# T04_Main_Board.net
KiCad netlist of a schematic drawn in EAGLE
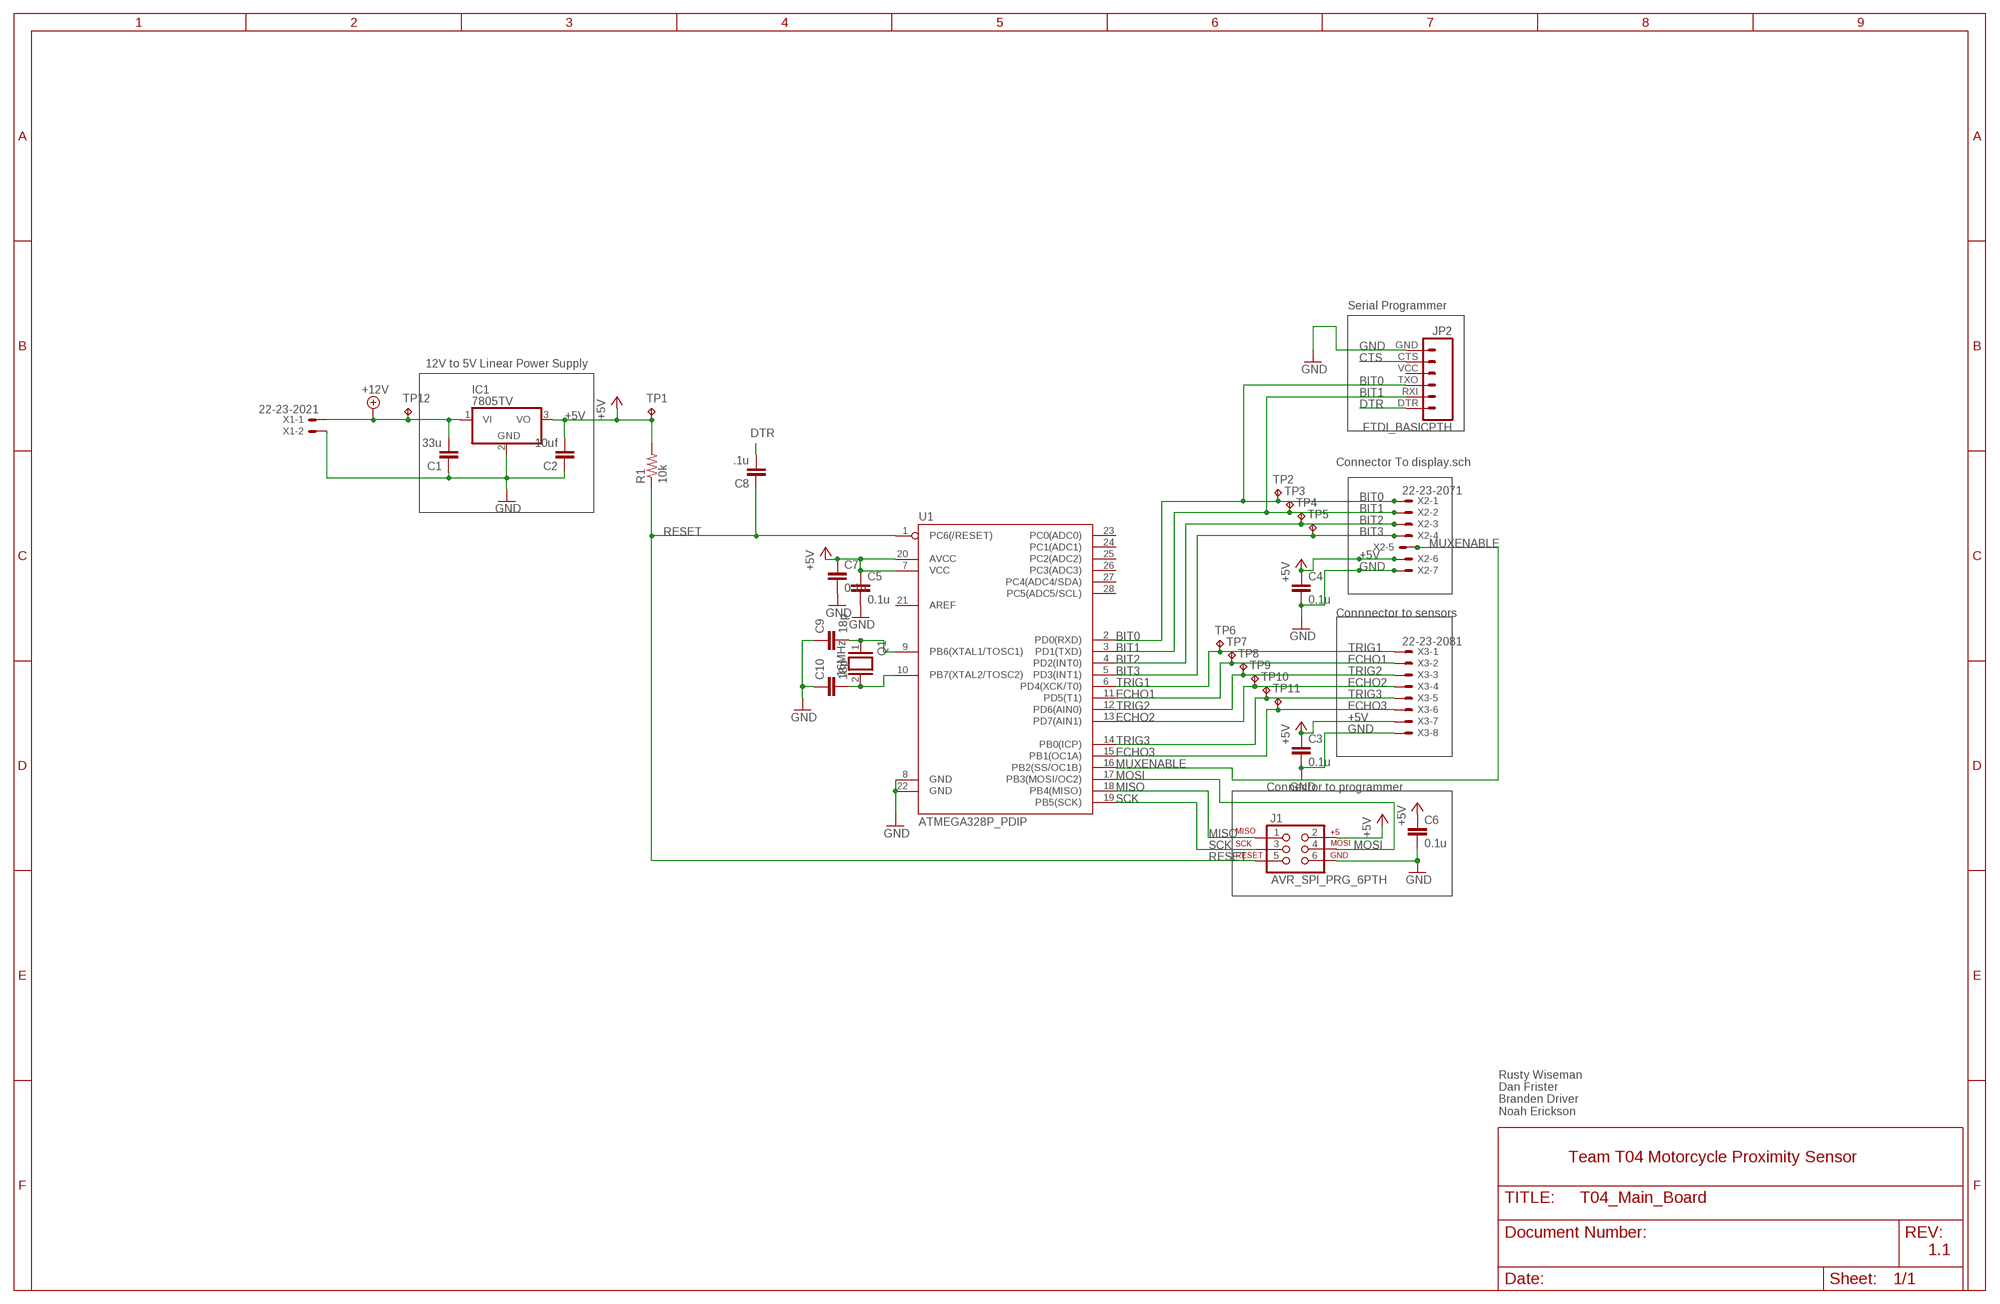
[diagram p0: schematic, sheet 1]

(export (version "E")
  (design (tool "Eeschema 10.0.6"))
  (components
    (comp (ref "C1")
      (value "33u")
      (footprint "eagle-import:C1206")
      (libsource (lib "eagle-import") (part "C-EUC1206"))
    )
    (comp (ref "C2")
      (value "10uf")
      (footprint "eagle-import:C1206")
      (libsource (lib "eagle-import") (part "C-EUC1206"))
    )
    (comp (ref "C3")
      (value "0.1u")
      (footprint "eagle-import:C1206")
      (libsource (lib "eagle-import") (part "C-EUC1206"))
    )
    (comp (ref "C4")
      (value "0.1u")
      (footprint "eagle-import:C1206")
      (libsource (lib "eagle-import") (part "C-EUC1206"))
    )
    (comp (ref "C5")
      (value "0.1u")
      (footprint "eagle-import:C1206")
      (libsource (lib "eagle-import") (part "C-EUC1206"))
    )
    (comp (ref "C6")
      (value "0.1u")
      (footprint "eagle-import:C1206")
      (libsource (lib "eagle-import") (part "C-EUC1206"))
    )
    (comp (ref "C7")
      (value "0.1u")
      (footprint "eagle-import:C1206")
      (libsource (lib "eagle-import") (part "C-EUC1206"))
    )
    (comp (ref "C8")
      (value ".1u")
      (footprint "eagle-import:C1206")
      (libsource (lib "eagle-import") (part "C-EUC1206"))
    )
    (comp (ref "C9")
      (value "18p")
      (footprint "eagle-import:C1206")
      (libsource (lib "eagle-import") (part "C-EUC1206"))
    )
    (comp (ref "C10")
      (value "18p")
      (footprint "eagle-import:C1206")
      (libsource (lib "eagle-import") (part "C-EUC1206"))
    )
    (comp (ref "IC1")
      (value "7805TV")
      (footprint "eagle-import:TO220V")
      (libsource (lib "eagle-import") (part "78TV05"))
    )
    (comp (ref "J1")
      (value "AVR_SPI_PRG_6PTH")
      (footprint "eagle-import:2X3")
      (libsource (lib "eagle-import") (part "AVR_SPI_PRG_6PTH"))
    )
    (comp (ref "JP2")
      (value "FTDI_BASICPTH")
      (footprint "eagle-import:FTDI_BASIC")
      (libsource (lib "eagle-import") (part "FTDI_BASICPTH"))
    )
    (comp (ref "Q1")
      (value "16MHz")
      (footprint "eagle-import:QS")
      (libsource (lib "eagle-import") (part "XTAL/S"))
    )
    (comp (ref "R1")
      (value "10k")
      (footprint "eagle-import:R1206")
      (libsource (lib "eagle-import") (part "R-US_R1206"))
    )
    (comp (ref "TP1")
      (value "TPB1,27")
      (footprint "eagle-import:B1,27")
      (libsource (lib "eagle-import") (part "TPB1,27"))
    )
    (comp (ref "TP2")
      (value "TPB1,27")
      (footprint "eagle-import:B1,27")
      (libsource (lib "eagle-import") (part "TPB1,27"))
    )
    (comp (ref "TP3")
      (value "TPB1,27")
      (footprint "eagle-import:B1,27")
      (libsource (lib "eagle-import") (part "TPB1,27"))
    )
    (comp (ref "TP4")
      (value "TPB1,27")
      (footprint "eagle-import:B1,27")
      (libsource (lib "eagle-import") (part "TPB1,27"))
    )
    (comp (ref "TP5")
      (value "TPB1,27")
      (footprint "eagle-import:B1,27")
      (libsource (lib "eagle-import") (part "TPB1,27"))
    )
    (comp (ref "TP6")
      (value "TPB1,27")
      (footprint "eagle-import:B1,27")
      (libsource (lib "eagle-import") (part "TPB1,27"))
    )
    (comp (ref "TP7")
      (value "TPB1,27")
      (footprint "eagle-import:B1,27")
      (libsource (lib "eagle-import") (part "TPB1,27"))
    )
    (comp (ref "TP8")
      (value "TPB1,27")
      (footprint "eagle-import:B1,27")
      (libsource (lib "eagle-import") (part "TPB1,27"))
    )
    (comp (ref "TP9")
      (value "TPB1,27")
      (footprint "eagle-import:B1,27")
      (libsource (lib "eagle-import") (part "TPB1,27"))
    )
    (comp (ref "TP10")
      (value "TPB1,27")
      (footprint "eagle-import:B1,27")
      (libsource (lib "eagle-import") (part "TPB1,27"))
    )
    (comp (ref "TP11")
      (value "TPB1,27")
      (footprint "eagle-import:B1,27")
      (libsource (lib "eagle-import") (part "TPB1,27"))
    )
    (comp (ref "TP12")
      (value "TPB1,27")
      (footprint "eagle-import:B1,27")
      (libsource (lib "eagle-import") (part "TPB1,27"))
    )
    (comp (ref "U1")
      (value "ATMEGA328P_PDIP")
      (footprint "eagle-import:DIL28-3")
      (libsource (lib "eagle-import") (part "ATMEGA328P_PDIP"))
    )
    (comp (ref "X1")
      (value "22-23-2021")
      (footprint "eagle-import:22-23-2021")
      (fields (field (name "MF") "MOLEX"))
      (libsource (lib "eagle-import") (part "22-23-2021"))
    )
    (comp (ref "X2")
      (value "22-23-2071")
      (footprint "eagle-import:22-23-2071")
      (fields (field (name "MF") "MOLEX"))
      (libsource (lib "eagle-import") (part "22-23-2071"))
    )
    (comp (ref "X3")
      (value "22-23-2081")
      (footprint "eagle-import:22-23-2081")
      (fields (field (name "MF") "MOLEX"))
      (libsource (lib "eagle-import") (part "22-23-2081"))
    )
  )
  (nets
    (net (code "1") (name "+5V") (class "Default")
      (node (ref "C2") (pin "2") (pinfunction "2_2") (pintype "passive"))
      (node (ref "C3") (pin "1") (pinfunction "1_1") (pintype "passive"))
      (node (ref "C4") (pin "1") (pinfunction "1_1") (pintype "passive"))
      (node (ref "C5") (pin "1") (pinfunction "1_1") (pintype "passive"))
      (node (ref "C6") (pin "1") (pinfunction "1_1") (pintype "passive"))
      (node (ref "C7") (pin "1") (pinfunction "1_1") (pintype "passive"))
      (node (ref "IC1") (pin "3") (pinfunction "VO_3") (pintype "passive"))
      (node (ref "J1") (pin "2") (pinfunction "2_2") (pintype "passive"))
      (node (ref "R1") (pin "2") (pinfunction "2_2") (pintype "passive"))
      (node (ref "TP1") (pin "TP") (pinfunction "TP_TP") (pintype "input"))
      (node (ref "U1") (pin "20") (pinfunction "AVCC_20") (pintype "bidirectional"))
      (node (ref "U1") (pin "7") (pinfunction "VCC_7") (pintype "bidirectional"))
      (node (ref "X2") (pin "6") (pinfunction "S_6") (pintype "passive"))
      (node (ref "X3") (pin "7") (pinfunction "S_7") (pintype "passive"))
    )
    (net (code "2") (name "+12V") (class "Default")
      (node (ref "C1") (pin "2") (pinfunction "2_2") (pintype "passive"))
      (node (ref "IC1") (pin "1") (pinfunction "VI_1") (pintype "input"))
      (node (ref "TP12") (pin "TP") (pinfunction "TP_TP") (pintype "input"))
      (node (ref "X1") (pin "1") (pinfunction "S_1") (pintype "passive"))
    )
    (net (code "3") (name "/BIT0") (class "Default")
      (node (ref "JP2") (pin "TXO") (pinfunction "3_TXO") (pintype "passive"))
      (node (ref "TP2") (pin "TP") (pinfunction "TP_TP") (pintype "input"))
      (node (ref "U1") (pin "2") (pinfunction "PD0(RXD)_2") (pintype "bidirectional"))
      (node (ref "X2") (pin "1") (pinfunction "S_1") (pintype "passive"))
    )
    (net (code "4") (name "/BIT1") (class "Default")
      (node (ref "JP2") (pin "RXI") (pinfunction "2_RXI") (pintype "passive"))
      (node (ref "TP3") (pin "TP") (pinfunction "TP_TP") (pintype "input"))
      (node (ref "U1") (pin "3") (pinfunction "PD1(TXD)_3") (pintype "bidirectional"))
      (node (ref "X2") (pin "2") (pinfunction "S_2") (pintype "passive"))
    )
    (net (code "5") (name "/BIT2") (class "Default")
      (node (ref "TP4") (pin "TP") (pinfunction "TP_TP") (pintype "input"))
      (node (ref "U1") (pin "4") (pinfunction "PD2(INT0)_4") (pintype "bidirectional"))
      (node (ref "X2") (pin "3") (pinfunction "S_3") (pintype "passive"))
    )
    (net (code "6") (name "/BIT3") (class "Default")
      (node (ref "TP5") (pin "TP") (pinfunction "TP_TP") (pintype "input"))
      (node (ref "U1") (pin "5") (pinfunction "PD3(INT1)_5") (pintype "bidirectional"))
      (node (ref "X2") (pin "4") (pinfunction "S_4") (pintype "passive"))
    )
    (net (code "7") (name "/CTS") (class "Default")
      (node (ref "JP2") (pin "CTS") (pinfunction "5_CTS") (pintype "passive"))
    )
    (net (code "8") (name "/DTR") (class "Default")
      (node (ref "C8") (pin "2") (pinfunction "2_2") (pintype "passive"))
      (node (ref "JP2") (pin "DTR") (pinfunction "1_DTR") (pintype "passive"))
    )
    (net (code "9") (name "/ECHO1") (class "Default")
      (node (ref "TP7") (pin "TP") (pinfunction "TP_TP") (pintype "input"))
      (node (ref "U1") (pin "11") (pinfunction "PD5(T1)_11") (pintype "bidirectional"))
      (node (ref "X3") (pin "2") (pinfunction "S_2") (pintype "passive"))
    )
    (net (code "10") (name "/ECHO2") (class "Default")
      (node (ref "TP9") (pin "TP") (pinfunction "TP_TP") (pintype "input"))
      (node (ref "U1") (pin "13") (pinfunction "PD7(AIN1)_13") (pintype "bidirectional"))
      (node (ref "X3") (pin "4") (pinfunction "S_4") (pintype "passive"))
    )
    (net (code "11") (name "/ECHO3") (class "Default")
      (node (ref "TP11") (pin "TP") (pinfunction "TP_TP") (pintype "input"))
      (node (ref "U1") (pin "15") (pinfunction "PB1(OC1A)_15") (pintype "bidirectional"))
      (node (ref "X3") (pin "6") (pinfunction "S_6") (pintype "passive"))
    )
    (net (code "12") (name "/MISO") (class "Default")
      (node (ref "J1") (pin "1") (pinfunction "1_1") (pintype "passive"))
      (node (ref "U1") (pin "18") (pinfunction "PB4(MISO)_18") (pintype "bidirectional"))
    )
    (net (code "13") (name "/MOSI") (class "Default")
      (node (ref "J1") (pin "4") (pinfunction "4_4") (pintype "passive"))
      (node (ref "U1") (pin "17") (pinfunction "PB3(MOSI/OC2)_17") (pintype "bidirectional"))
    )
    (net (code "14") (name "/MUXENABLE") (class "Default")
      (node (ref "U1") (pin "16") (pinfunction "PB2(SS/OC1B)_16") (pintype "bidirectional"))
      (node (ref "X2") (pin "5") (pinfunction "S_5") (pintype "passive"))
    )
    (net (code "15") (name "/RESET") (class "Default")
      (node (ref "C8") (pin "1") (pinfunction "1_1") (pintype "passive"))
      (node (ref "J1") (pin "5") (pinfunction "5_5") (pintype "passive"))
      (node (ref "R1") (pin "1") (pinfunction "1_1") (pintype "passive"))
      (node (ref "U1") (pin "1") (pinfunction "PC6(/RESET)_1") (pintype "bidirectional"))
    )
    (net (code "16") (name "/SCK") (class "Default")
      (node (ref "J1") (pin "3") (pinfunction "3_3") (pintype "passive"))
      (node (ref "U1") (pin "19") (pinfunction "PB5(SCK)_19") (pintype "bidirectional"))
    )
    (net (code "17") (name "/TRIG1") (class "Default")
      (node (ref "TP6") (pin "TP") (pinfunction "TP_TP") (pintype "input"))
      (node (ref "U1") (pin "6") (pinfunction "PD4(XCK/T0)_6") (pintype "bidirectional"))
      (node (ref "X3") (pin "1") (pinfunction "S_1") (pintype "passive"))
    )
    (net (code "18") (name "/TRIG2") (class "Default")
      (node (ref "TP8") (pin "TP") (pinfunction "TP_TP") (pintype "input"))
      (node (ref "U1") (pin "12") (pinfunction "PD6(AIN0)_12") (pintype "bidirectional"))
      (node (ref "X3") (pin "3") (pinfunction "S_3") (pintype "passive"))
    )
    (net (code "19") (name "/TRIG3") (class "Default")
      (node (ref "TP10") (pin "TP") (pinfunction "TP_TP") (pintype "input"))
      (node (ref "U1") (pin "14") (pinfunction "PB0(ICP)_14") (pintype "bidirectional"))
      (node (ref "X3") (pin "5") (pinfunction "S_5") (pintype "passive"))
    )
    (net (code "20") (name "GND") (class "Default")
      (node (ref "C1") (pin "1") (pinfunction "1_1") (pintype "passive"))
      (node (ref "C10") (pin "1") (pinfunction "1_1") (pintype "passive"))
      (node (ref "C2") (pin "1") (pinfunction "1_1") (pintype "passive"))
      (node (ref "C3") (pin "2") (pinfunction "2_2") (pintype "passive"))
      (node (ref "C4") (pin "2") (pinfunction "2_2") (pintype "passive"))
      (node (ref "C5") (pin "2") (pinfunction "2_2") (pintype "passive"))
      (node (ref "C6") (pin "2") (pinfunction "2_2") (pintype "passive"))
      (node (ref "C7") (pin "2") (pinfunction "2_2") (pintype "passive"))
      (node (ref "C9") (pin "1") (pinfunction "1_1") (pintype "passive"))
      (node (ref "IC1") (pin "2") (pinfunction "GND_2") (pintype "passive"))
      (node (ref "J1") (pin "6") (pinfunction "6_6") (pintype "passive"))
      (node (ref "JP2") (pin "GND") (pinfunction "6_GND") (pintype "passive"))
      (node (ref "U1") (pin "22") (pinfunction "GND_22") (pintype "bidirectional"))
      (node (ref "U1") (pin "8") (pinfunction "GND_8") (pintype "bidirectional"))
      (node (ref "X1") (pin "2") (pinfunction "S_2") (pintype "passive"))
      (node (ref "X2") (pin "7") (pinfunction "S_7") (pintype "passive"))
      (node (ref "X3") (pin "8") (pinfunction "S_8") (pintype "passive"))
    )
    (net (code "21") (name "Net-(U1-PB6(XTAL1{slash}TOSC1))") (class "Default")
      (node (ref "C9") (pin "2") (pinfunction "2_2") (pintype "passive"))
      (node (ref "Q1") (pin "1") (pinfunction "1_1") (pintype "passive"))
      (node (ref "U1") (pin "9") (pinfunction "PB6(XTAL1/TOSC1)_9") (pintype "bidirectional"))
    )
    (net (code "22") (name "Net-(U1-PB7(XTAL2{slash}TOSC2))") (class "Default")
      (node (ref "C10") (pin "2") (pinfunction "2_2") (pintype "passive"))
      (node (ref "Q1") (pin "2") (pinfunction "2_2") (pintype "passive"))
      (node (ref "U1") (pin "10") (pinfunction "PB7(XTAL2/TOSC2)_10") (pintype "bidirectional"))
    )
    (net (code "23") (name "unconnected-(JP2-4-PadVCC)") (class "Default")
      (node (ref "JP2") (pin "VCC") (pinfunction "4_VCC") (pintype "passive"))
    )
    (net (code "24") (name "unconnected-(U1-AREF-Pad21)") (class "Default")
      (node (ref "U1") (pin "21") (pinfunction "AREF_21") (pintype "bidirectional"))
    )
    (net (code "25") (name "unconnected-(U1-PC0(ADC0)-Pad23)") (class "Default")
      (node (ref "U1") (pin "23") (pinfunction "PC0(ADC0)_23") (pintype "bidirectional"))
    )
    (net (code "26") (name "unconnected-(U1-PC1(ADC1)-Pad24)") (class "Default")
      (node (ref "U1") (pin "24") (pinfunction "PC1(ADC1)_24") (pintype "bidirectional"))
    )
    (net (code "27") (name "unconnected-(U1-PC2(ADC2)-Pad25)") (class "Default")
      (node (ref "U1") (pin "25") (pinfunction "PC2(ADC2)_25") (pintype "bidirectional"))
    )
    (net (code "28") (name "unconnected-(U1-PC3(ADC3)-Pad26)") (class "Default")
      (node (ref "U1") (pin "26") (pinfunction "PC3(ADC3)_26") (pintype "bidirectional"))
    )
    (net (code "29") (name "unconnected-(U1-PC4(ADC4{slash}SDA)-Pad27)") (class "Default")
      (node (ref "U1") (pin "27") (pinfunction "PC4(ADC4/SDA)_27") (pintype "bidirectional"))
    )
    (net (code "30") (name "unconnected-(U1-PC5(ADC5{slash}SCL)-Pad28)") (class "Default")
      (node (ref "U1") (pin "28") (pinfunction "PC5(ADC5/SCL)_28") (pintype "bidirectional"))
    )
  )
)
